# Misc.net
KiCad netlist of a schematic drawn in Altium Designer
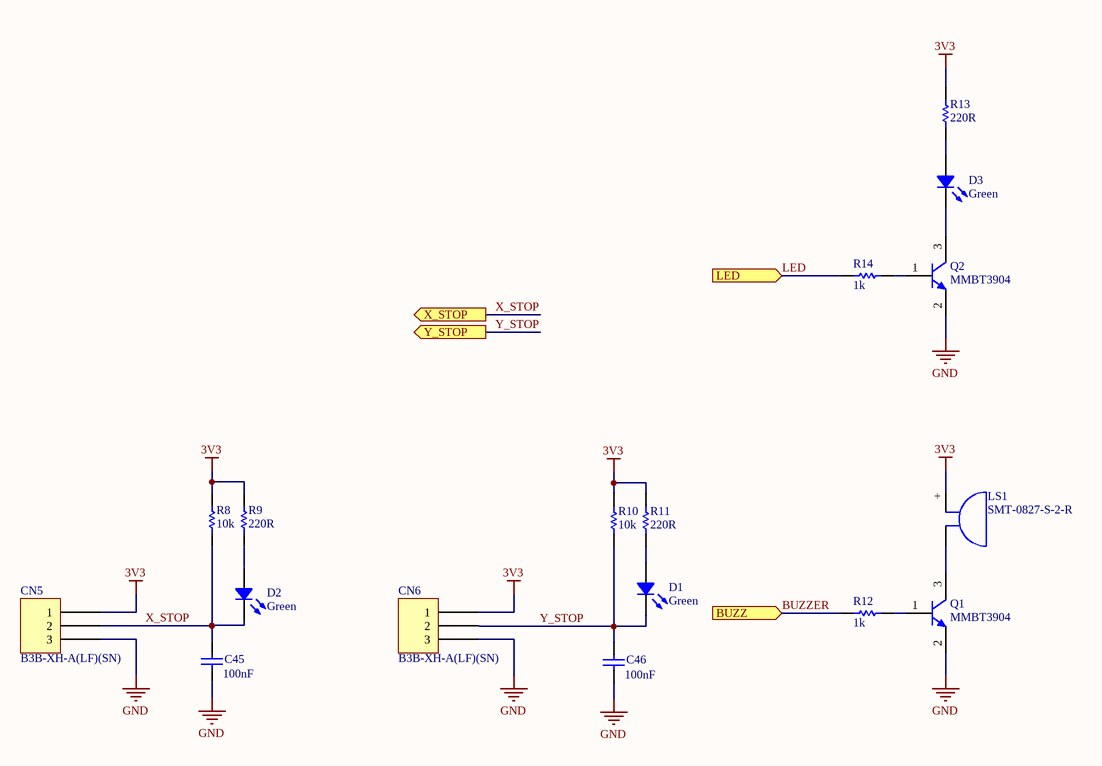
[diagram p0: Misc.SchDoc]

(export (version "E")
  (design (tool "Eeschema 10.0.6"))
  (components
    (comp (ref "C45")
      (value "100nF")
      (footprint "1608[0603]")
      (description "Capacitor")
      (fields (field (name "Comment") "X5R") (field (name "PUBLISHER") "Altium Limited"))
      (libsource (lib "Miscellaneous Devices") (part "Cap"))
    )
    (comp (ref "C46")
      (value "100nF")
      (footprint "1608[0603]")
      (description "Capacitor")
      (fields (field (name "Comment") "X5R") (field (name "PUBLISHER") "Altium Limited"))
      (libsource (lib "Miscellaneous Devices") (part "Cap"))
    )
    (comp (ref "CN5")
      (value "B3B-XH-A(LF)(SN)")
      (footprint "JST XH B3B-XH-A")
      (description "CONN HEADER VERT 3POS 2.5MM")
      (fields (field (name "MANUFACTURER") "JST Sales America Inc."))
      (libsource (lib "Celestial Altium Library - altium_library") (part "3 Pin"))
    )
    (comp (ref "CN6")
      (value "B3B-XH-A(LF)(SN)")
      (footprint "JST XH B3B-XH-A")
      (description "CONN HEADER VERT 3POS 2.5MM")
      (fields (field (name "MANUFACTURER") "JST Sales America Inc."))
      (libsource (lib "Celestial Altium Library - altium_library") (part "3 Pin"))
    )
    (comp (ref "D1")
      (value "Green")
      (footprint "LED 0805_2012 GREEN")
      (description "LED GREEN CLEAR 0805 SMD")
      (fields
        (field (name "PART NUMBER") "QTLP630C4TR")
        (field (name "MANUFACTURER") "Everlight Electronics Co Ltd")
      )
      (libsource (lib "Celestial Altium Library - altium_library") (part "LED"))
    )
    (comp (ref "D2")
      (value "Green")
      (footprint "LED 0805_2012 GREEN")
      (description "LED GREEN CLEAR 0805 SMD")
      (fields
        (field (name "PART NUMBER") "QTLP630C4TR")
        (field (name "MANUFACTURER") "Everlight Electronics Co Ltd")
      )
      (libsource (lib "Celestial Altium Library - altium_library") (part "LED"))
    )
    (comp (ref "D3")
      (value "Green")
      (footprint "LED 0805_2012 GREEN")
      (description "LED GREEN CLEAR 0805 SMD")
      (fields
        (field (name "PART NUMBER") "QTLP630C4TR")
        (field (name "MANUFACTURER") "Everlight Electronics Co Ltd")
      )
      (libsource (lib "Celestial Altium Library - altium_library") (part "LED"))
    )
    (comp (ref "LS1")
      (value "SMT-0827-S-2-R")
      (footprint "PUI Audio SMT-0827-S-2-R")
      (description "AUDIO MAGNETIC XDCR 2.5-4.5V SMD")
      (fields (field (name "MANUFACTURER") "PUI Audio, Inc."))
      (libsource (lib "Celestial Altium Library - altium_library") (part "Buzzer 2 pin"))
    )
    (comp (ref "Q1")
      (value "MMBT3904")
      (footprint "SOT-23_N")
      (description "TRANS NPN 40V 0.2A SOT416")
      (fields (field (name "PART NUMBER") "MMBT3904TT1G") (field (name "MANUFACTURER") "ON Semiconductor"))
      (libsource (lib "Celestial Altium Library - altium_library") (part "ON SEMI NPN SC-75"))
    )
    (comp (ref "Q2")
      (value "MMBT3904")
      (footprint "SOT-23_N")
      (description "TRANS NPN 40V 0.2A SOT416")
      (fields (field (name "PART NUMBER") "MMBT3904TT1G") (field (name "MANUFACTURER") "ON Semiconductor"))
      (libsource (lib "Celestial Altium Library - altium_library") (part "ON SEMI NPN SC-75"))
    )
    (comp (ref "R8")
      (value "10k")
      (footprint "1608[0603]")
      (description "Resistor")
      (fields (field (name "Comment") "Res1") (field (name "PUBLISHER") "Altium Limited"))
      (libsource (lib "Miscellaneous Devices") (part "Res1"))
    )
    (comp (ref "R9")
      (value "220R")
      (footprint "1608[0603]")
      (description "Resistor")
      (fields (field (name "Comment") "Res1") (field (name "PUBLISHER") "Altium Limited"))
      (libsource (lib "Miscellaneous Devices") (part "Res1"))
    )
    (comp (ref "R10")
      (value "10k")
      (footprint "1608[0603]")
      (description "Resistor")
      (fields (field (name "Comment") "Res1") (field (name "PUBLISHER") "Altium Limited"))
      (libsource (lib "Miscellaneous Devices") (part "Res1"))
    )
    (comp (ref "R11")
      (value "220R")
      (footprint "1608[0603]")
      (description "Resistor")
      (fields (field (name "Comment") "Res1") (field (name "PUBLISHER") "Altium Limited"))
      (libsource (lib "Miscellaneous Devices") (part "Res1"))
    )
    (comp (ref "R12")
      (value "1k")
      (footprint "1608[0603]")
      (description "Resistor")
      (fields (field (name "Comment") "Res1") (field (name "PUBLISHER") "Altium Limited"))
      (libsource (lib "Miscellaneous Devices") (part "Res1"))
    )
    (comp (ref "R13")
      (value "220R")
      (footprint "1608[0603]")
      (description "Resistor")
      (fields (field (name "Comment") "Res1") (field (name "PUBLISHER") "Altium Limited"))
      (libsource (lib "Miscellaneous Devices") (part "Res1"))
    )
    (comp (ref "R14")
      (value "1k")
      (footprint "1608[0603]")
      (description "Resistor")
      (fields (field (name "Comment") "Res1") (field (name "PUBLISHER") "Altium Limited"))
      (libsource (lib "Miscellaneous Devices") (part "Res1"))
    )
  )
  (nets
    (net (code "1") (name "/BUZZER") (class "Default")
      (node (ref "R12") (pin "1") (pinfunction "1_1") (pintype "passive"))
    )
    (net (code "2") (name "/LED") (class "Default")
      (node (ref "R14") (pin "1") (pinfunction "1_1") (pintype "passive"))
    )
    (net (code "3") (name "/X_STOP") (class "Default")
      (node (ref "C45") (pin "1") (pinfunction "1_1") (pintype "passive"))
      (node (ref "CN5") (pin "2") (pinfunction "2_2") (pintype "passive"))
      (node (ref "D2") (pin "2") (pinfunction "2_2") (pintype "passive"))
      (node (ref "R8") (pin "2") (pinfunction "2_2") (pintype "passive"))
    )
    (net (code "4") (name "/Y_STOP") (class "Default")
      (node (ref "C46") (pin "1") (pinfunction "1_1") (pintype "passive"))
      (node (ref "CN6") (pin "2") (pinfunction "2_2") (pintype "passive"))
      (node (ref "D1") (pin "2") (pinfunction "2_2") (pintype "passive"))
      (node (ref "R10") (pin "2") (pinfunction "2_2") (pintype "passive"))
    )
    (net (code "5") (name "3V3") (class "Default")
      (node (ref "CN5") (pin "1") (pinfunction "1_1") (pintype "passive"))
      (node (ref "CN6") (pin "1") (pinfunction "1_1") (pintype "passive"))
      (node (ref "LS1") (pin "+") (pinfunction "+_+") (pintype "passive"))
      (node (ref "R10") (pin "1") (pinfunction "1_1") (pintype "passive"))
      (node (ref "R11") (pin "1") (pinfunction "1_1") (pintype "passive"))
      (node (ref "R13") (pin "1") (pinfunction "1_1") (pintype "passive"))
      (node (ref "R8") (pin "1") (pinfunction "1_1") (pintype "passive"))
      (node (ref "R9") (pin "1") (pinfunction "1_1") (pintype "passive"))
    )
    (net (code "6") (name "GND") (class "Default")
      (node (ref "C45") (pin "2") (pinfunction "2_2") (pintype "passive"))
      (node (ref "C46") (pin "2") (pinfunction "2_2") (pintype "passive"))
      (node (ref "CN5") (pin "3") (pinfunction "3_3") (pintype "passive"))
      (node (ref "CN6") (pin "3") (pinfunction "3_3") (pintype "passive"))
      (node (ref "Q1") (pin "2") (pinfunction "E_2") (pintype "passive"))
      (node (ref "Q2") (pin "2") (pinfunction "E_2") (pintype "passive"))
    )
    (net (code "7") (name "Net-(D1-Pad1)") (class "Default")
      (node (ref "D1") (pin "1") (pinfunction "1_1") (pintype "passive"))
      (node (ref "R11") (pin "2") (pinfunction "2_2") (pintype "passive"))
    )
    (net (code "8") (name "Net-(D2-Pad1)") (class "Default")
      (node (ref "D2") (pin "1") (pinfunction "1_1") (pintype "passive"))
      (node (ref "R9") (pin "2") (pinfunction "2_2") (pintype "passive"))
    )
    (net (code "9") (name "Net-(D3-Pad1)") (class "Default")
      (node (ref "D3") (pin "1") (pinfunction "1_1") (pintype "passive"))
      (node (ref "R13") (pin "2") (pinfunction "2_2") (pintype "passive"))
    )
    (net (code "10") (name "Net-(Q1-B)") (class "Default")
      (node (ref "Q1") (pin "1") (pinfunction "B_1") (pintype "passive"))
      (node (ref "R12") (pin "2") (pinfunction "2_2") (pintype "passive"))
    )
    (net (code "11") (name "Net-(Q1-C)") (class "Default")
      (node (ref "LS1") (pin "-") (pinfunction "-_-") (pintype "passive"))
      (node (ref "Q1") (pin "3") (pinfunction "C_3") (pintype "passive"))
    )
    (net (code "12") (name "Net-(Q2-B)") (class "Default")
      (node (ref "Q2") (pin "1") (pinfunction "B_1") (pintype "passive"))
      (node (ref "R14") (pin "2") (pinfunction "2_2") (pintype "passive"))
    )
    (net (code "13") (name "Net-(Q2-C)") (class "Default")
      (node (ref "D3") (pin "2") (pinfunction "2_2") (pintype "passive"))
      (node (ref "Q2") (pin "3") (pinfunction "C_3") (pintype "passive"))
    )
  )
)
